# pic_board.net
KiCad netlist of a schematic drawn in EAGLE
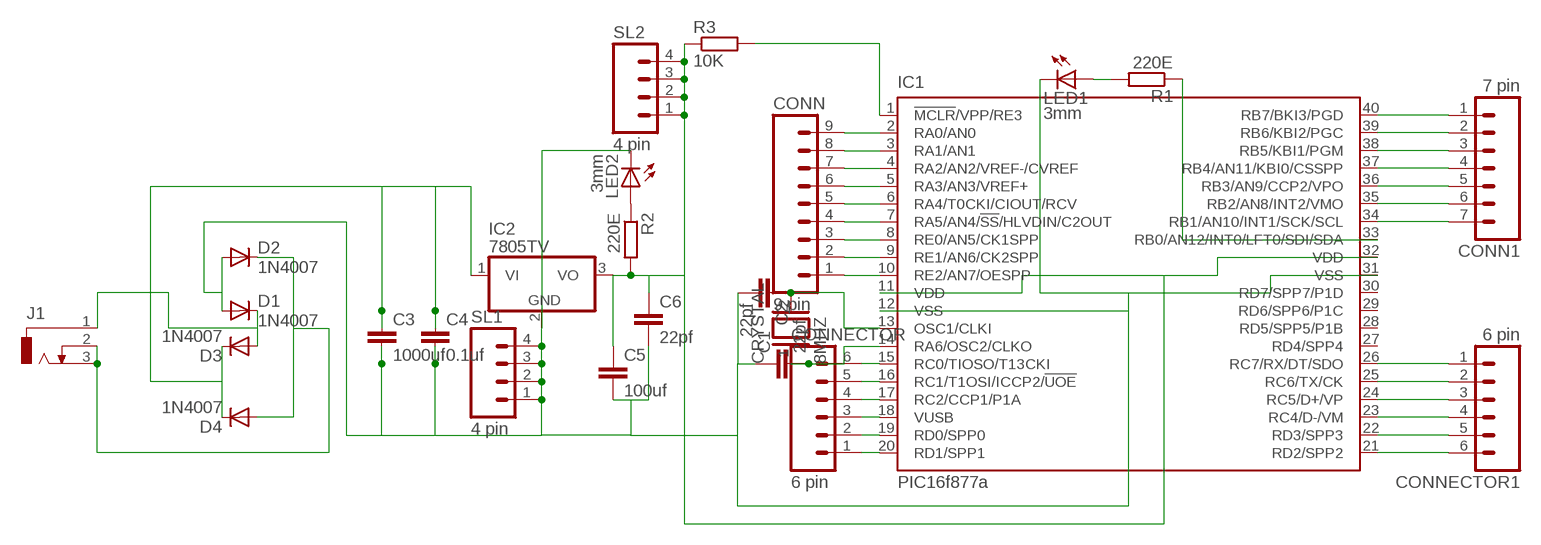
[diagram p0: schematic, sheet 1]

(export (version "E")
  (design (tool "Eeschema 10.0.6"))
  (components
    (comp (ref "C1")
      (value "22pf")
      (footprint "eagle-import:C2.5-2")
      (libsource (lib "eagle-import") (part "C2.5/2"))
    )
    (comp (ref "C2")
      (value "22pf")
      (footprint "eagle-import:C2.5-2")
      (libsource (lib "eagle-import") (part "C2.5/2"))
    )
    (comp (ref "C3")
      (value "1000uf")
      (footprint "eagle-import:C5B7.2")
      (libsource (lib "eagle-import") (part "C5/7.2"))
    )
    (comp (ref "C4")
      (value "0.1uf")
      (footprint "eagle-import:C2.5-3")
      (libsource (lib "eagle-import") (part "C2,5-3"))
    )
    (comp (ref "C5")
      (value "100uf")
      (footprint "eagle-import:C5B7.2")
      (libsource (lib "eagle-import") (part "C5/7.2"))
    )
    (comp (ref "C6")
      (value "22pf")
      (footprint "eagle-import:C2.5-2")
      (libsource (lib "eagle-import") (part "C2.5/2"))
    )
    (comp (ref "CONN")
      (value "9 pin")
      (footprint "eagle-import:09P")
      (libsource (lib "eagle-import") (part "M09"))
    )
    (comp (ref "CONN1")
      (value "7 pin")
      (footprint "eagle-import:07P")
      (libsource (lib "eagle-import") (part "M07"))
    )
    (comp (ref "CONNECTOR")
      (value "6 pin")
      (footprint "eagle-import:06P")
      (libsource (lib "eagle-import") (part "M06"))
    )
    (comp (ref "CONNECTOR1")
      (value "6 pin")
      (footprint "eagle-import:06P")
      (fields (field (name "OC_FARNELL") "unknown") (field (name "OC_NEWARK") "unknown"))
      (libsource (lib "eagle-import") (part "M06"))
    )
    (comp (ref "CRYSTAL")
      (value "8MHZ")
      (footprint "eagle-import:QS")
      (libsource (lib "eagle-import") (part "XTAL/S"))
    )
    (comp (ref "D1")
      (value "1N4007")
      (footprint "eagle-import:DO41-10")
      (libsource (lib "eagle-import") (part "1N4004"))
    )
    (comp (ref "D2")
      (value "1N4007")
      (footprint "eagle-import:DO41-10")
      (libsource (lib "eagle-import") (part "1N4004"))
    )
    (comp (ref "D3")
      (value "1N4007")
      (footprint "eagle-import:DO41-10")
      (libsource (lib "eagle-import") (part "1N4004"))
    )
    (comp (ref "D4")
      (value "1N4007")
      (footprint "eagle-import:DO41-10")
      (libsource (lib "eagle-import") (part "1N4004"))
    )
    (comp (ref "IC1")
      (value "PIC16f877a")
      (footprint "eagle-import:DIL40")
      (fields (field (name "MF") "MICROCHIP") (field (name "MPN") "PIC18F4455-I/P"))
      (libsource (lib "eagle-import") (part "PIC18F4_40455"))
    )
    (comp (ref "IC2")
      (value "7805TV")
      (footprint "eagle-import:TO220V")
      (libsource (lib "eagle-import") (part "78TV05"))
    )
    (comp (ref "J1")
      (value "DCJ0303")
      (footprint "eagle-import:DCJ0303")
      (libsource (lib "eagle-import") (part "DCJ0303"))
    )
    (comp (ref "LED1")
      (value "3mm")
      (footprint "eagle-import:LED3MM")
      (libsource (lib "eagle-import") (part "LED3MM"))
    )
    (comp (ref "LED2")
      (value "3mm")
      (footprint "eagle-import:LED3MM")
      (libsource (lib "eagle-import") (part "LED3MM"))
    )
    (comp (ref "R1")
      (value "220E")
      (footprint "eagle-import:0204_7")
      (libsource (lib "eagle-import") (part "R-EU_0204/7"))
    )
    (comp (ref "R2")
      (value "220E")
      (footprint "eagle-import:0204_7")
      (libsource (lib "eagle-import") (part "R-EU_0204/7"))
    )
    (comp (ref "R3")
      (value "10K")
      (footprint "eagle-import:0204_7")
      (libsource (lib "eagle-import") (part "R-EU_0204/7"))
    )
    (comp (ref "SL1")
      (value "4 pin")
      (footprint "eagle-import:04P")
      (libsource (lib "eagle-import") (part "M04"))
    )
    (comp (ref "SL2")
      (value "4 pin")
      (footprint "eagle-import:04P")
      (libsource (lib "eagle-import") (part "M04"))
    )
  )
  (nets
    (net (code "1") (name "Net-(D1-PadC)") (class "Default")
      (node (ref "D1") (pin "C") (pinfunction "C_C") (pintype "passive"))
      (node (ref "D3") (pin "A") (pinfunction "A_A") (pintype "passive"))
      (node (ref "J1") (pin "1") (pinfunction "1_1") (pintype "passive"))
    )
    (net (code "2") (name "Net-(D2-PadC)") (class "Default")
      (node (ref "D2") (pin "C") (pinfunction "C_C") (pintype "passive"))
      (node (ref "D4") (pin "A") (pinfunction "A_A") (pintype "passive"))
      (node (ref "J1") (pin "2") (pinfunction "2_2") (pintype "passive"))
      (node (ref "J1") (pin "3") (pinfunction "3_3") (pintype "passive"))
    )
    (net (code "3") (name "Net-(IC1-OSC1{slash}CLKI)") (class "Default")
      (node (ref "C2") (pin "1") (pinfunction "1_1") (pintype "passive"))
      (node (ref "CRYSTAL") (pin "2") (pinfunction "2_2") (pintype "passive"))
      (node (ref "IC1") (pin "13") (pinfunction "OSC1/CLKI_13") (pintype "input"))
    )
    (net (code "4") (name "Net-(IC1-RA0{slash}AN0)") (class "Default")
      (node (ref "CONN") (pin "9") (pinfunction "9_9") (pintype "passive"))
      (node (ref "IC1") (pin "2") (pinfunction "RA0/AN0_2") (pintype "bidirectional"))
    )
    (net (code "5") (name "Net-(IC1-RA1{slash}AN1)") (class "Default")
      (node (ref "CONN") (pin "8") (pinfunction "8_8") (pintype "passive"))
      (node (ref "IC1") (pin "3") (pinfunction "RA1/AN1_3") (pintype "bidirectional"))
    )
    (net (code "6") (name "Net-(IC1-RA2{slash}AN2{slash}VREF-{slash}CVREF)") (class "Default")
      (node (ref "CONN") (pin "7") (pinfunction "7_7") (pintype "passive"))
      (node (ref "IC1") (pin "4") (pinfunction "RA2/AN2/VREF-/CVREF_4") (pintype "bidirectional"))
    )
    (net (code "7") (name "Net-(IC1-RA3{slash}AN3{slash}VREF+)") (class "Default")
      (node (ref "CONN") (pin "6") (pinfunction "6_6") (pintype "passive"))
      (node (ref "IC1") (pin "5") (pinfunction "RA3/AN3/VREF+_5") (pintype "bidirectional"))
    )
    (net (code "8") (name "Net-(IC1-RA4{slash}T0CKI{slash}CIOUT{slash}RCV)") (class "Default")
      (node (ref "CONN") (pin "5") (pinfunction "5_5") (pintype "passive"))
      (node (ref "IC1") (pin "6") (pinfunction "RA4/T0CKI/CIOUT/RCV_6") (pintype "bidirectional"))
    )
    (net (code "9") (name "Net-(IC1-RA5{slash}AN4{slash}~{SS}{slash}HLVDIN{slash}C2OUT)") (class "Default")
      (node (ref "CONN") (pin "4") (pinfunction "4_4") (pintype "passive"))
      (node (ref "IC1") (pin "7") (pinfunction "RA5/AN4/~{SS}/HLVDIN/C2OUT_7") (pintype "bidirectional"))
    )
    (net (code "10") (name "Net-(IC1-RA6{slash}OSC2{slash}CLKO)") (class "Default")
      (node (ref "C1") (pin "2") (pinfunction "2_2") (pintype "passive"))
      (node (ref "CRYSTAL") (pin "1") (pinfunction "1_1") (pintype "passive"))
      (node (ref "IC1") (pin "14") (pinfunction "RA6/OSC2/CLKO_14") (pintype "output"))
    )
    (net (code "11") (name "Net-(IC1-RB0{slash}AN12{slash}INT0{slash}LFT0{slash}SDI{slash}SDA)") (class "Default")
      (node (ref "IC1") (pin "33") (pinfunction "RB0/AN12/INT0/LFT0/SDI/SDA_33") (pintype "bidirectional"))
      (node (ref "R1") (pin "1") (pinfunction "1_1") (pintype "passive"))
    )
    (net (code "12") (name "Net-(IC1-RB1{slash}AN10{slash}INT1{slash}SCK{slash}SCL)") (class "Default")
      (node (ref "CONN1") (pin "7") (pinfunction "7_7") (pintype "passive"))
      (node (ref "IC1") (pin "34") (pinfunction "RB1/AN10/INT1/SCK/SCL_34") (pintype "bidirectional"))
    )
    (net (code "13") (name "Net-(IC1-RB2{slash}AN8{slash}INT2{slash}VMO)") (class "Default")
      (node (ref "CONN1") (pin "6") (pinfunction "6_6") (pintype "passive"))
      (node (ref "IC1") (pin "35") (pinfunction "RB2/AN8/INT2/VMO_35") (pintype "bidirectional"))
    )
    (net (code "14") (name "Net-(IC1-RB3{slash}AN9{slash}CCP2{slash}VPO)") (class "Default")
      (node (ref "CONN1") (pin "5") (pinfunction "5_5") (pintype "passive"))
      (node (ref "IC1") (pin "36") (pinfunction "RB3/AN9/CCP2/VPO_36") (pintype "bidirectional"))
    )
    (net (code "15") (name "Net-(IC1-RB4{slash}AN11{slash}KBI0{slash}CSSPP)") (class "Default")
      (node (ref "CONN1") (pin "4") (pinfunction "4_4") (pintype "passive"))
      (node (ref "IC1") (pin "37") (pinfunction "RB4/AN11/KBI0/CSSPP_37") (pintype "bidirectional"))
    )
    (net (code "16") (name "Net-(IC1-RB5{slash}KBI1{slash}PGM)") (class "Default")
      (node (ref "CONN1") (pin "3") (pinfunction "3_3") (pintype "passive"))
      (node (ref "IC1") (pin "38") (pinfunction "RB5/KBI1/PGM_38") (pintype "bidirectional"))
    )
    (net (code "17") (name "Net-(IC1-RB6{slash}KBI2{slash}PGC)") (class "Default")
      (node (ref "CONN1") (pin "2") (pinfunction "2_2") (pintype "passive"))
      (node (ref "IC1") (pin "39") (pinfunction "RB6/KBI2/PGC_39") (pintype "bidirectional"))
    )
    (net (code "18") (name "Net-(IC1-RB7{slash}BKI3{slash}PGD)") (class "Default")
      (node (ref "CONN1") (pin "1") (pinfunction "1_1") (pintype "passive"))
      (node (ref "IC1") (pin "40") (pinfunction "RB7/BKI3/PGD_40") (pintype "bidirectional"))
    )
    (net (code "19") (name "Net-(IC1-RC0{slash}TIOSO{slash}T13CKI)") (class "Default")
      (node (ref "CONNECTOR") (pin "6") (pinfunction "6_6") (pintype "passive"))
      (node (ref "IC1") (pin "15") (pinfunction "RC0/TIOSO/T13CKI_15") (pintype "bidirectional"))
    )
    (net (code "20") (name "Net-(IC1-RC1{slash}T1OSI{slash}ICCP2{slash}~{UOE})") (class "Default")
      (node (ref "CONNECTOR") (pin "5") (pinfunction "5_5") (pintype "passive"))
      (node (ref "IC1") (pin "16") (pinfunction "RC1/T1OSI/ICCP2/~{UOE}_16") (pintype "bidirectional"))
    )
    (net (code "21") (name "Net-(IC1-RC2{slash}CCP1{slash}P1A)") (class "Default")
      (node (ref "CONNECTOR") (pin "4") (pinfunction "4_4") (pintype "passive"))
      (node (ref "IC1") (pin "17") (pinfunction "RC2/CCP1/P1A_17") (pintype "bidirectional"))
    )
    (net (code "22") (name "Net-(IC1-RC4{slash}D-{slash}VM)") (class "Default")
      (node (ref "CONNECTOR1") (pin "4") (pinfunction "4_4") (pintype "passive"))
      (node (ref "IC1") (pin "23") (pinfunction "RC4/D-/VM_23") (pintype "bidirectional"))
    )
    (net (code "23") (name "Net-(IC1-RC5{slash}D+{slash}VP)") (class "Default")
      (node (ref "CONNECTOR1") (pin "3") (pinfunction "3_3") (pintype "passive"))
      (node (ref "IC1") (pin "24") (pinfunction "RC5/D+/VP_24") (pintype "bidirectional"))
    )
    (net (code "24") (name "Net-(IC1-RC6{slash}TX{slash}CK)") (class "Default")
      (node (ref "CONNECTOR1") (pin "2") (pinfunction "2_2") (pintype "passive"))
      (node (ref "IC1") (pin "25") (pinfunction "RC6/TX/CK_25") (pintype "bidirectional"))
    )
    (net (code "25") (name "Net-(IC1-RC7{slash}RX{slash}DT{slash}SDO)") (class "Default")
      (node (ref "CONNECTOR1") (pin "1") (pinfunction "1_1") (pintype "passive"))
      (node (ref "IC1") (pin "26") (pinfunction "RC7/RX/DT/SDO_26") (pintype "bidirectional"))
    )
    (net (code "26") (name "Net-(IC1-RD0{slash}SPP0)") (class "Default")
      (node (ref "CONNECTOR") (pin "2") (pinfunction "2_2") (pintype "passive"))
      (node (ref "IC1") (pin "19") (pinfunction "RD0/SPP0_19") (pintype "bidirectional"))
    )
    (net (code "27") (name "Net-(IC1-RD1{slash}SPP1)") (class "Default")
      (node (ref "CONNECTOR") (pin "1") (pinfunction "1_1") (pintype "passive"))
      (node (ref "IC1") (pin "20") (pinfunction "RD1/SPP1_20") (pintype "bidirectional"))
    )
    (net (code "28") (name "Net-(IC1-RD2{slash}SPP2)") (class "Default")
      (node (ref "CONNECTOR1") (pin "6") (pinfunction "6_6") (pintype "passive"))
      (node (ref "IC1") (pin "21") (pinfunction "RD2/SPP2_21") (pintype "bidirectional"))
    )
    (net (code "29") (name "Net-(IC1-RD3{slash}SPP3)") (class "Default")
      (node (ref "CONNECTOR1") (pin "5") (pinfunction "5_5") (pintype "passive"))
      (node (ref "IC1") (pin "22") (pinfunction "RD3/SPP3_22") (pintype "bidirectional"))
    )
    (net (code "30") (name "Net-(IC1-RE0{slash}AN5{slash}CK1SPP)") (class "Default")
      (node (ref "CONN") (pin "3") (pinfunction "3_3") (pintype "passive"))
      (node (ref "IC1") (pin "8") (pinfunction "RE0/AN5/CK1SPP_8") (pintype "bidirectional"))
    )
    (net (code "31") (name "Net-(IC1-RE1{slash}AN6{slash}CK2SPP)") (class "Default")
      (node (ref "CONN") (pin "2") (pinfunction "2_2") (pintype "passive"))
      (node (ref "IC1") (pin "9") (pinfunction "RE1/AN6/CK2SPP_9") (pintype "bidirectional"))
    )
    (net (code "32") (name "Net-(IC1-RE2{slash}AN7{slash}OESPP)") (class "Default")
      (node (ref "CONN") (pin "1") (pinfunction "1_1") (pintype "passive"))
      (node (ref "IC1") (pin "10") (pinfunction "RE2/AN7/OESPP_10") (pintype "bidirectional"))
    )
    (net (code "33") (name "Net-(IC1-VUSB)") (class "Default")
      (node (ref "CONNECTOR") (pin "3") (pinfunction "3_3") (pintype "passive"))
      (node (ref "IC1") (pin "18") (pinfunction "VUSB_18") (pintype "bidirectional"))
    )
    (net (code "34") (name "Net-(IC1-~{MCLR}{slash}VPP{slash}RE3)") (class "Default")
      (node (ref "IC1") (pin "1") (pinfunction "~{MCLR}/VPP/RE3_1") (pintype "input"))
      (node (ref "R3") (pin "2") (pinfunction "2_2") (pintype "passive"))
    )
    (net (code "35") (name "Net-(IC2-GND)") (class "Default")
      (node (ref "C1") (pin "1") (pinfunction "1_1") (pintype "passive"))
      (node (ref "C2") (pin "2") (pinfunction "2_2") (pintype "passive"))
      (node (ref "C3") (pin "2") (pinfunction "2_2") (pintype "passive"))
      (node (ref "C4") (pin "2") (pinfunction "2_2") (pintype "passive"))
      (node (ref "C5") (pin "2") (pinfunction "2_2") (pintype "passive"))
      (node (ref "C6") (pin "2") (pinfunction "2_2") (pintype "passive"))
      (node (ref "D1") (pin "A") (pinfunction "A_A") (pintype "passive"))
      (node (ref "D2") (pin "A") (pinfunction "A_A") (pintype "passive"))
      (node (ref "IC1") (pin "12") (pinfunction "VSS_12") (pintype "power_in"))
      (node (ref "IC1") (pin "31") (pinfunction "VSS_31") (pintype "power_in"))
      (node (ref "IC2") (pin "2") (pinfunction "GND_2") (pintype "passive"))
      (node (ref "LED1") (pin "K") (pinfunction "C_K") (pintype "passive"))
      (node (ref "LED2") (pin "K") (pinfunction "C_K") (pintype "passive"))
      (node (ref "SL1") (pin "1") (pinfunction "1_1") (pintype "passive"))
      (node (ref "SL1") (pin "2") (pinfunction "2_2") (pintype "passive"))
      (node (ref "SL1") (pin "3") (pinfunction "3_3") (pintype "passive"))
      (node (ref "SL1") (pin "4") (pinfunction "4_4") (pintype "passive"))
    )
    (net (code "36") (name "Net-(IC2-VI)") (class "Default")
      (node (ref "C3") (pin "1") (pinfunction "1_1") (pintype "passive"))
      (node (ref "C4") (pin "1") (pinfunction "1_1") (pintype "passive"))
      (node (ref "D3") (pin "C") (pinfunction "C_C") (pintype "passive"))
      (node (ref "D4") (pin "C") (pinfunction "C_C") (pintype "passive"))
      (node (ref "IC2") (pin "1") (pinfunction "VI_1") (pintype "input"))
    )
    (net (code "37") (name "Net-(IC2-VO)") (class "Default")
      (node (ref "C5") (pin "1") (pinfunction "1_1") (pintype "passive"))
      (node (ref "C6") (pin "1") (pinfunction "1_1") (pintype "passive"))
      (node (ref "IC1") (pin "11") (pinfunction "VDD_11") (pintype "power_in"))
      (node (ref "IC1") (pin "32") (pinfunction "VDD_32") (pintype "power_in"))
      (node (ref "IC2") (pin "3") (pinfunction "VO_3") (pintype "passive"))
      (node (ref "R2") (pin "2") (pinfunction "2_2") (pintype "passive"))
      (node (ref "R3") (pin "1") (pinfunction "1_1") (pintype "passive"))
      (node (ref "SL2") (pin "1") (pinfunction "1_1") (pintype "passive"))
      (node (ref "SL2") (pin "2") (pinfunction "2_2") (pintype "passive"))
      (node (ref "SL2") (pin "3") (pinfunction "3_3") (pintype "passive"))
      (node (ref "SL2") (pin "4") (pinfunction "4_4") (pintype "passive"))
    )
    (net (code "38") (name "Net-(LED1-PadA)") (class "Default")
      (node (ref "LED1") (pin "A") (pinfunction "A_A") (pintype "passive"))
      (node (ref "R1") (pin "2") (pinfunction "2_2") (pintype "passive"))
    )
    (net (code "39") (name "Net-(LED2-PadA)") (class "Default")
      (node (ref "LED2") (pin "A") (pinfunction "A_A") (pintype "passive"))
      (node (ref "R2") (pin "1") (pinfunction "1_1") (pintype "passive"))
    )
    (net (code "40") (name "unconnected-(IC1-RD4{slash}SPP4-Pad27)") (class "Default")
      (node (ref "IC1") (pin "27") (pinfunction "RD4/SPP4_27") (pintype "bidirectional"))
    )
    (net (code "41") (name "unconnected-(IC1-RD5{slash}SPP5{slash}P1B-Pad28)") (class "Default")
      (node (ref "IC1") (pin "28") (pinfunction "RD5/SPP5/P1B_28") (pintype "bidirectional"))
    )
    (net (code "42") (name "unconnected-(IC1-RD6{slash}SPP6{slash}P1C-Pad29)") (class "Default")
      (node (ref "IC1") (pin "29") (pinfunction "RD6/SPP6/P1C_29") (pintype "bidirectional"))
    )
    (net (code "43") (name "unconnected-(IC1-RD7{slash}SPP7{slash}P1D-Pad30)") (class "Default")
      (node (ref "IC1") (pin "30") (pinfunction "RD7/SPP7/P1D_30") (pintype "bidirectional"))
    )
  )
)
